# Jack_Mount.net
KiCad netlist of a schematic drawn in EAGLE
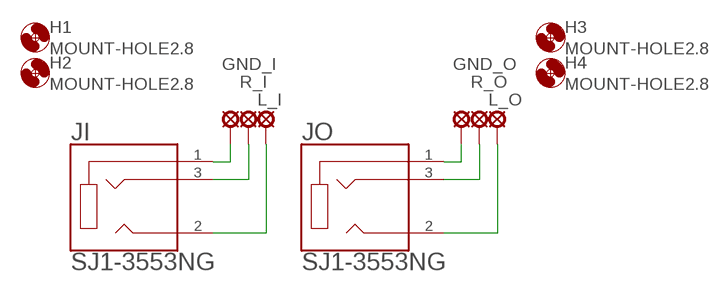
[diagram p0: schematic, sheet 1]

(export (version "E")
  (design (tool "Eeschema 10.0.6"))
  (components
    (comp (ref "GND_I")
      (value "LSP10")
      (footprint "eagle-import:LSP10")
      (libsource (lib "eagle-import") (part "LSP10"))
    )
    (comp (ref "GND_O")
      (value "LSP10")
      (footprint "eagle-import:LSP10")
      (libsource (lib "eagle-import") (part "LSP10"))
    )
    (comp (ref "H1")
      (value "MOUNT-HOLE2.8")
      (footprint "eagle-import:2,8")
      (libsource (lib "eagle-import") (part "MOUNT-HOLE2.8"))
    )
    (comp (ref "H2")
      (value "MOUNT-HOLE2.8")
      (footprint "eagle-import:2,8")
      (libsource (lib "eagle-import") (part "MOUNT-HOLE2.8"))
    )
    (comp (ref "H3")
      (value "MOUNT-HOLE2.8")
      (footprint "eagle-import:2,8")
      (libsource (lib "eagle-import") (part "MOUNT-HOLE2.8"))
    )
    (comp (ref "H4")
      (value "MOUNT-HOLE2.8")
      (footprint "eagle-import:2,8")
      (libsource (lib "eagle-import") (part "MOUNT-HOLE2.8"))
    )
    (comp (ref "JI")
      (value "SJ1-3553NG")
      (footprint "eagle-import:CUI_SJ1-3553NG")
      (fields (field (name "MF") "CUI Devices"))
      (libsource (lib "eagle-import") (part "SJ1-3553NG"))
    )
    (comp (ref "JO")
      (value "SJ1-3553NG")
      (footprint "eagle-import:CUI_SJ1-3553NG")
      (fields (field (name "MF") "CUI Devices"))
      (libsource (lib "eagle-import") (part "SJ1-3553NG"))
    )
    (comp (ref "L_I")
      (value "LSP10")
      (footprint "eagle-import:LSP10")
      (libsource (lib "eagle-import") (part "LSP10"))
    )
    (comp (ref "L_O")
      (value "LSP10")
      (footprint "eagle-import:LSP10")
      (libsource (lib "eagle-import") (part "LSP10"))
    )
    (comp (ref "R_I")
      (value "LSP10")
      (footprint "eagle-import:LSP10")
      (libsource (lib "eagle-import") (part "LSP10"))
    )
    (comp (ref "R_O")
      (value "LSP10")
      (footprint "eagle-import:LSP10")
      (libsource (lib "eagle-import") (part "LSP10"))
    )
  )
  (nets
    (net (code "1") (name "Net-(GND_I-PadMP)") (class "Default")
      (node (ref "GND_I") (pin "MP") (pinfunction "MP_MP") (pintype "passive"))
      (node (ref "JI") (pin "1") (pinfunction "1_1") (pintype "passive"))
    )
    (net (code "2") (name "Net-(GND_O-PadMP)") (class "Default")
      (node (ref "GND_O") (pin "MP") (pinfunction "MP_MP") (pintype "passive"))
      (node (ref "JO") (pin "1") (pinfunction "1_1") (pintype "passive"))
    )
    (net (code "3") (name "Net-(JI-Pad2)") (class "Default")
      (node (ref "JI") (pin "2") (pinfunction "2_2") (pintype "passive"))
      (node (ref "L_I") (pin "MP") (pinfunction "MP_MP") (pintype "passive"))
    )
    (net (code "4") (name "Net-(JI-Pad3)") (class "Default")
      (node (ref "JI") (pin "3") (pinfunction "3_3") (pintype "passive"))
      (node (ref "R_I") (pin "MP") (pinfunction "MP_MP") (pintype "passive"))
    )
    (net (code "5") (name "Net-(JO-Pad2)") (class "Default")
      (node (ref "JO") (pin "2") (pinfunction "2_2") (pintype "passive"))
      (node (ref "L_O") (pin "MP") (pinfunction "MP_MP") (pintype "passive"))
    )
    (net (code "6") (name "Net-(JO-Pad3)") (class "Default")
      (node (ref "JO") (pin "3") (pinfunction "3_3") (pintype "passive"))
      (node (ref "R_O") (pin "MP") (pinfunction "MP_MP") (pintype "passive"))
    )
  )
)
